# Buck.net
KiCad netlist of a schematic drawn in Altium Designer
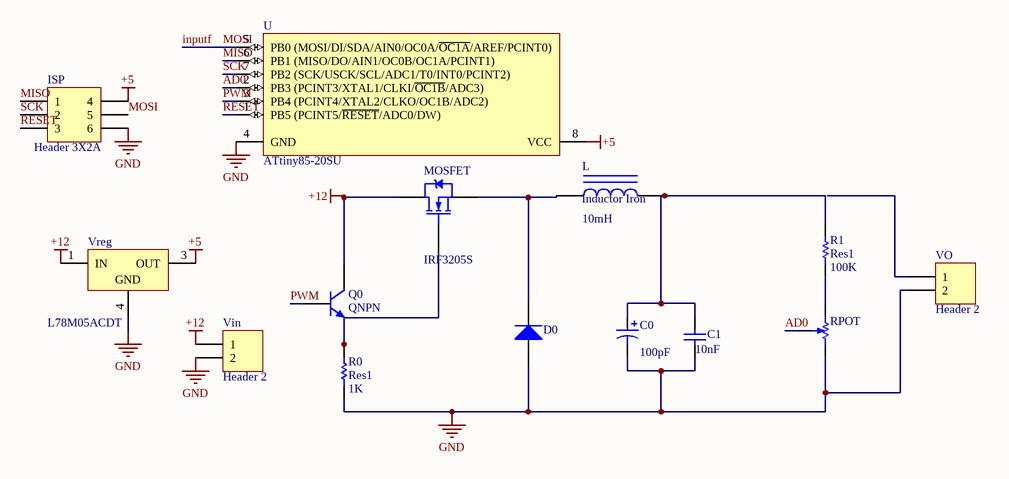
[diagram p0: Buck.SchDoc]

(export (version "E")
  (design (tool "Eeschema 10.0.6"))
  (components
    (comp (ref "C0")
      (value "100pF")
      (footprint "RAD-0.2")
      (description "Polarized Capacitor (Radial)")
      (fields (field (name "Comment") "Cap Pol1") (field (name "PUBLISHER") "Altium Limited"))
      (libsource (lib "Miscellaneous Devices") (part "Cap Pol1"))
    )
    (comp (ref "C1")
      (value "10nF")
      (footprint "RB7.6-15")
      (description "Capacitor")
      (fields (field (name "Comment") "Cap") (field (name "PUBLISHER") "Altium Limited"))
      (libsource (lib "Miscellaneous Devices") (part "Cap"))
    )
    (comp (ref "D0")
      (value "Diode BAS16")
      (footprint "SOT-23_L")
      (description "Silicon Switching Diode for High-Speed Switching")
      (fields (field (name "PUBLISHER") "Altium Limited"))
      (libsource (lib "Miscellaneous Devices") (part "Diode BAS16"))
    )
    (comp (ref "ISP")
      (value "Header 3X2A")
      (footprint "HDR2X3_CEN")
      (description "Header, 3-Pin, Dual row")
      (fields (field (name "PUBLISHER") "Altium Limited"))
      (libsource (lib "Miscellaneous Connectors") (part "Header 3X2A"))
    )
    (comp (ref "L")
      (value "Inductor Iron")
      (footprint "AXIAL-0.9")
      (description "Magnetic-Core Inductor")
      (fields (field (name "ALTIUM_VALUE") "10mH") (field (name "PUBLISHER") "Altium Limited"))
      (libsource (lib "Miscellaneous Devices") (part "Inductor Iron"))
    )
    (comp (ref "MOSFET")
      (value "IRF3205S")
      (footprint "D2PAK_L")
      (description "HEXFET Power MOSFET")
      (fields (field (name "PUBLISHER") "Altium Limited"))
      (libsource (lib "IR Discrete MOSFET - Power") (part "IRF3205S"))
    )
    (comp (ref "Q0")
      (value "QNPN")
      (footprint "SOT-23B_L")
      (description "NPN Bipolar Transistor")
      (fields (field (name "PUBLISHER") "Altium Limited"))
      (libsource (lib "Miscellaneous Devices") (part "QNPN"))
    )
    (comp (ref "R0")
      (value "Res1")
      (footprint "j1-0603")
      (description "Resistor")
      (fields (field (name "ALTIUM_VALUE") "1K") (field (name "PUBLISHER") "Altium Limited"))
      (libsource (lib "Miscellaneous Devices") (part "Res1"))
    )
    (comp (ref "R1")
      (value "Res1")
      (footprint "j1-0603")
      (description "Resistor")
      (fields (field (name "ALTIUM_VALUE") "100K") (field (name "PUBLISHER") "Altium Limited"))
      (libsource (lib "Miscellaneous Devices") (part "Res1"))
    )
    (comp (ref "RPOT")
      (value "RPot SM")
      (footprint "POT4MM-2")
      (description "Square Trimming Potentiometer")
      (fields (field (name "PUBLISHER") "Altium Limited"))
      (libsource (lib "Miscellaneous Devices") (part "RPot SM"))
    )
    (comp (ref "U")
      (value "ATtiny85-20SU")
      (footprint "8S2_L")
      (fields (field (name "PUBLISHER") "Altium Limited"))
      (libsource (lib "Atmel Microcontroller 8-Bit tinyAVR") (part "ATtiny85-20SU"))
    )
    (comp (ref "Vin")
      (value "Header 2")
      (footprint "HDR1X2")
      (description "Header, 2-Pin")
      (fields (field (name "PUBLISHER") "Altium Limited"))
      (libsource (lib "Miscellaneous Connectors") (part "Header 2"))
    )
    (comp (ref "VO")
      (value "Header 2")
      (footprint "HDR1X2")
      (description "Header, 2-Pin")
      (fields (field (name "PUBLISHER") "Altium Limited"))
      (libsource (lib "Miscellaneous Connectors") (part "Header 2"))
    )
    (comp (ref "Vreg")
      (value "L78M05ACDT")
      (footprint "TO-252")
      (description "Precision 500mA Regulator")
      (fields (field (name "PUBLISHER") "Altium Limited"))
      (libsource (lib "ST Power Mgt Voltage Regulator") (part "L78M05ACDT"))
    )
  )
  (nets
    (net (code "1") (name "+5") (class "Default")
      (node (ref "ISP") (pin "4") (pinfunction "4_4") (pintype "passive"))
      (node (ref "U") (pin "8") (pinfunction "VCC_8") (pintype "power_in"))
      (node (ref "Vreg") (pin "3") (pinfunction "OUT_3") (pintype "power_in"))
    )
    (net (code "2") (name "+12") (class "Default")
      (node (ref "MOSFET") (pin "2") (pinfunction "D_2") (pintype "passive"))
      (node (ref "Q0") (pin "1") (pinfunction "C_1") (pintype "passive"))
      (node (ref "Vin") (pin "1") (pinfunction "1_1") (pintype "passive"))
      (node (ref "Vreg") (pin "1") (pinfunction "IN_1") (pintype "power_in"))
    )
    (net (code "3") (name "/AD0") (class "Default")
      (node (ref "RPOT") (pin "W") (pinfunction "W_W") (pintype "passive"))
      (node (ref "U") (pin "2") (pinfunction "PB3_(PCINT3/XTAL1/CLKI/~{OC1B}/ADC3)_2") (pintype "bidirectional"))
    )
    (net (code "4") (name "/MISO") (class "Default")
      (node (ref "ISP") (pin "1") (pinfunction "1_1") (pintype "passive"))
      (node (ref "U") (pin "6") (pinfunction "PB1_(MISO/DO/AIN1/OC0B/OC1A/PCINT1)_6") (pintype "bidirectional"))
    )
    (net (code "5") (name "/MOSI") (class "Default")
      (node (ref "ISP") (pin "5") (pinfunction "5_5") (pintype "passive"))
      (node (ref "U") (pin "5") (pinfunction "PB0_(MOSI/DI/SDA/AIN0/OC0A/~{OC1A}/AREF/PCINT0)_5") (pintype "bidirectional"))
    )
    (net (code "6") (name "/PWM") (class "Default")
      (node (ref "Q0") (pin "2") (pinfunction "B_2") (pintype "passive"))
      (node (ref "U") (pin "3") (pinfunction "PB4_(PCINT4/XTAL2/CLKO/OC1B/ADC2)_3") (pintype "bidirectional"))
    )
    (net (code "7") (name "/RESET") (class "Default")
      (node (ref "ISP") (pin "3") (pinfunction "3_3") (pintype "passive"))
      (node (ref "U") (pin "1") (pinfunction "PB5_(PCINT5/~{RESET}/ADC0/DW)_1") (pintype "bidirectional"))
    )
    (net (code "8") (name "/SCK") (class "Default")
      (node (ref "ISP") (pin "2") (pinfunction "2_2") (pintype "passive"))
      (node (ref "U") (pin "7") (pinfunction "PB2_(SCK/USCK/SCL/ADC1/T0/INT0/PCINT2)_7") (pintype "bidirectional"))
    )
    (net (code "9") (name "GND") (class "Default")
      (node (ref "C0") (pin "2") (pinfunction "2_2") (pintype "passive"))
      (node (ref "C1") (pin "1") (pinfunction "1_1") (pintype "passive"))
      (node (ref "D0") (pin "1") (pinfunction "A_1") (pintype "passive"))
      (node (ref "ISP") (pin "6") (pinfunction "6_6") (pintype "passive"))
      (node (ref "R0") (pin "1") (pinfunction "1_1") (pintype "passive"))
      (node (ref "RPOT") (pin "CW") (pinfunction "+_CW") (pintype "passive"))
      (node (ref "U") (pin "4") (pinfunction "GND_4") (pintype "power_in"))
      (node (ref "VO") (pin "2") (pinfunction "2_2") (pintype "passive"))
      (node (ref "Vin") (pin "2") (pinfunction "2_2") (pintype "passive"))
      (node (ref "Vreg") (pin "4") (pinfunction "GND_4") (pintype "power_in"))
    )
    (net (code "10") (name "Net-(C0-Pad1)") (class "Default")
      (node (ref "C0") (pin "1") (pinfunction "1_1") (pintype "passive"))
      (node (ref "C1") (pin "2") (pinfunction "2_2") (pintype "passive"))
      (node (ref "L") (pin "2") (pinfunction "2_2") (pintype "passive"))
      (node (ref "R1") (pin "2") (pinfunction "2_2") (pintype "passive"))
    )
    (net (code "11") (name "Net-(D0-K)") (class "Default")
      (node (ref "D0") (pin "3") (pinfunction "K_3") (pintype "passive"))
      (node (ref "L") (pin "1") (pinfunction "1_1") (pintype "passive"))
      (node (ref "MOSFET") (pin "3") (pinfunction "S_3") (pintype "passive"))
    )
    (net (code "12") (name "Net-(MOSFET-G)") (class "Default")
      (node (ref "MOSFET") (pin "1") (pinfunction "G_1") (pintype "passive"))
      (node (ref "Q0") (pin "3") (pinfunction "E_3") (pintype "passive"))
      (node (ref "R0") (pin "2") (pinfunction "2_2") (pintype "passive"))
    )
    (net (code "13") (name "Net-(RPOT--)") (class "Default")
      (node (ref "R1") (pin "1") (pinfunction "1_1") (pintype "passive"))
      (node (ref "RPOT") (pin "CCW") (pinfunction "-_CCW") (pintype "passive"))
    )
    (net (code "14") (name "unconnected-(VO-Pad1)") (class "Default")
      (node (ref "VO") (pin "1") (pinfunction "1_1") (pintype "passive"))
    )
  )
)
